# Sallen-Key_Filter.net
KiCad netlist of a schematic drawn in Altium Designer
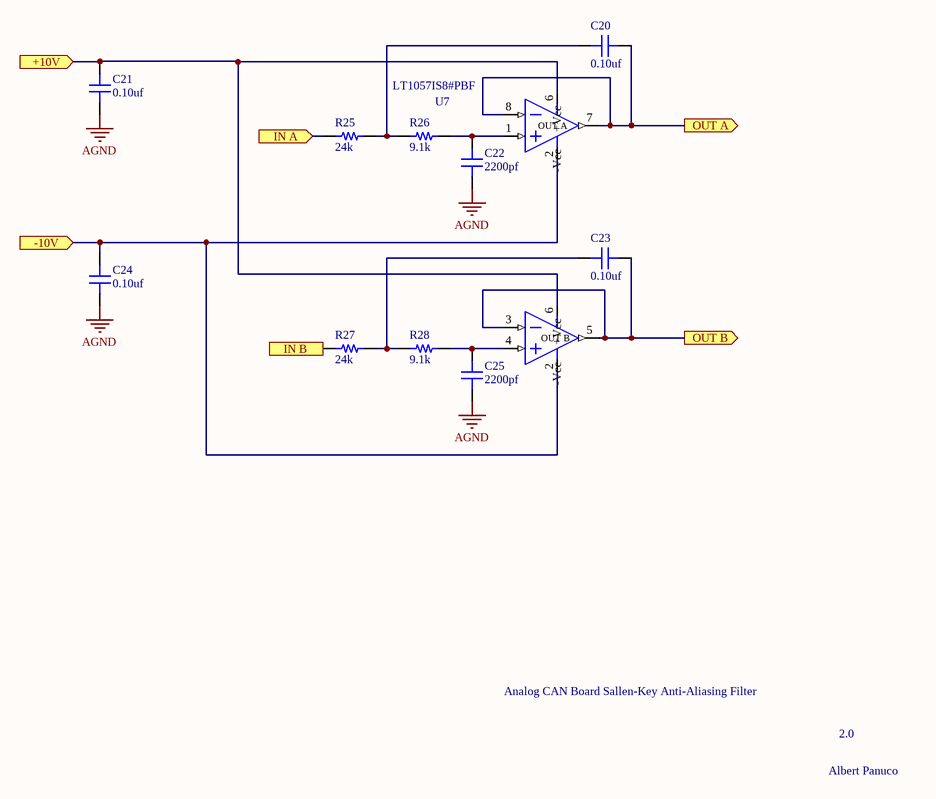
[diagram p0: Sallen-Key Filter.SchDoc]

(export (version "E")
  (design (tool "Eeschema 10.0.6"))
  (components
    (comp (ref "C20")
      (value "0.10uf")
      (footprint "CAP 0805/2012")
      (fields
        (field (name "Comment") "Capacitor MLCC 0.10uf 25V CAP 0805/2012")
        (field (name "CREATED_BY") "Nick Mah")
      )
      (libsource (lib "Altium-Lib") (part "Capacitor"))
    )
    (comp (ref "C21")
      (value "0.10uf")
      (footprint "CAP 0805/2012")
      (fields
        (field (name "Comment") "Capacitor MLCC 0.10uf 25V CAP 0805/2012")
        (field (name "CREATED_BY") "Nick Mah")
      )
      (libsource (lib "Altium-Lib") (part "Capacitor"))
    )
    (comp (ref "C22")
      (value "2200pf")
      (footprint "CAP 0805/2012")
      (fields
        (field (name "Comment") "Capacitor MLCC 2200pf 25V CAP 0805/2012")
        (field (name "CREATED_BY") "Nick Mah")
      )
      (libsource (lib "Altium-Lib") (part "Capacitor"))
    )
    (comp (ref "C23")
      (value "0.10uf")
      (footprint "CAP 0805/2012")
      (fields
        (field (name "Comment") "Capacitor MLCC 0.10uf 25V CAP 0805/2012")
        (field (name "CREATED_BY") "Nick Mah")
      )
      (libsource (lib "Altium-Lib") (part "Capacitor"))
    )
    (comp (ref "C24")
      (value "0.10uf")
      (footprint "CAP 0805/2012")
      (fields
        (field (name "Comment") "Capacitor MLCC 0.10uf 25V CAP 0805/2012")
        (field (name "CREATED_BY") "Nick Mah")
      )
      (libsource (lib "Altium-Lib") (part "Capacitor"))
    )
    (comp (ref "C25")
      (value "2200pf")
      (footprint "CAP 0805/2012")
      (fields
        (field (name "Comment") "Capacitor MLCC 2200pf 25V CAP 0805/2012")
        (field (name "CREATED_BY") "Nick Mah")
      )
      (libsource (lib "Altium-Lib") (part "Capacitor"))
    )
    (comp (ref "R25")
      (value "24k")
      (footprint "RES 0805/2012")
      (fields
        (field (name "TOLERANCE") "1%")
        (field (name "POWER") "1/10W")
        (field (name "Comment") "Resistor 24k 0805 1/10W 1%")
        (field (name "CREATED_BY") "Nick Mah")
      )
      (libsource (lib "Altium-Lib") (part "Resistor"))
    )
    (comp (ref "R26")
      (value "9.1k")
      (footprint "RES 0805/2012")
      (fields
        (field (name "TOLERANCE") "1%")
        (field (name "POWER") "1/10W")
        (field (name "Comment") "Resistor 9.1k 0805 1/10W 1%")
        (field (name "CREATED_BY") "Nick Mah")
      )
      (libsource (lib "Altium-Lib") (part "Resistor"))
    )
    (comp (ref "R27")
      (value "24k")
      (footprint "RES 0805/2012")
      (fields
        (field (name "TOLERANCE") "1%")
        (field (name "POWER") "1/10W")
        (field (name "Comment") "Resistor 24k 0805 1/10W 1%")
        (field (name "CREATED_BY") "Nick Mah")
      )
      (libsource (lib "Altium-Lib") (part "Resistor"))
    )
    (comp (ref "R28")
      (value "9.1k")
      (footprint "RES 0805/2012")
      (fields
        (field (name "TOLERANCE") "1%")
        (field (name "POWER") "1/10W")
        (field (name "Comment") "Resistor 9.1k 0805 1/10W 1%")
        (field (name "CREATED_BY") "Nick Mah")
      )
      (libsource (lib "Altium-Lib") (part "Resistor"))
    )
    (comp (ref "U7")
      (value "LT1057IS8#PBF")
      (footprint "SOIC-8")
      (description "IC OPAMP JFET 5MHZ 8SO")
      (fields (field (name "CREATED_BY") "Albert Panuco"))
      (libsource (lib "Altium-Lib") (part "LT1057IS8#PBF"))
    )
  )
  (nets
    (net (code "1") (name "/+10V") (class "Default")
      (node (ref "C21") (pin "2") (pinfunction "2_2") (pintype "passive"))
      (node (ref "U7") (pin "6") (pinfunction "+Vcc_6") (pintype "input"))
    )
    (net (code "2") (name "/-10V") (class "Default")
      (node (ref "C24") (pin "1") (pinfunction "1_1") (pintype "passive"))
      (node (ref "U7") (pin "2") (pinfunction "-Vcc_2") (pintype "input"))
    )
    (net (code "3") (name "/IN A") (class "Default")
      (node (ref "R25") (pin "1") (pinfunction "1_1") (pintype "passive"))
    )
    (net (code "4") (name "/IN B") (class "Default")
      (node (ref "R27") (pin "1") (pinfunction "1_1") (pintype "passive"))
    )
    (net (code "5") (name "/OUT A") (class "Default")
      (node (ref "C20") (pin "2") (pinfunction "2_2") (pintype "passive"))
      (node (ref "U7") (pin "7") (pinfunction "OUT_A_7") (pintype "output"))
      (node (ref "U7") (pin "8") (pinfunction "-IN_A_8") (pintype "input"))
    )
    (net (code "6") (name "/OUT B") (class "Default")
      (node (ref "C23") (pin "2") (pinfunction "2_2") (pintype "passive"))
      (node (ref "U7") (pin "3") (pinfunction "+IN_B_3") (pintype "input"))
      (node (ref "U7") (pin "5") (pinfunction "OUT_B_5") (pintype "output"))
    )
    (net (code "7") (name "AGND") (class "Default")
      (node (ref "C21") (pin "1") (pinfunction "1_1") (pintype "passive"))
      (node (ref "C22") (pin "1") (pinfunction "1_1") (pintype "passive"))
      (node (ref "C24") (pin "2") (pinfunction "2_2") (pintype "passive"))
      (node (ref "C25") (pin "1") (pinfunction "1_1") (pintype "passive"))
    )
    (net (code "8") (name "Net-(C20-Pad1)") (class "Default")
      (node (ref "C20") (pin "1") (pinfunction "1_1") (pintype "passive"))
      (node (ref "R25") (pin "2") (pinfunction "2_2") (pintype "passive"))
      (node (ref "R26") (pin "1") (pinfunction "1_1") (pintype "passive"))
    )
    (net (code "9") (name "Net-(C23-Pad1)") (class "Default")
      (node (ref "C23") (pin "1") (pinfunction "1_1") (pintype "passive"))
      (node (ref "R27") (pin "2") (pinfunction "2_2") (pintype "passive"))
      (node (ref "R28") (pin "1") (pinfunction "1_1") (pintype "passive"))
    )
    (net (code "10") (name "Net-(C25-Pad2)") (class "Default")
      (node (ref "C25") (pin "2") (pinfunction "2_2") (pintype "passive"))
      (node (ref "R28") (pin "2") (pinfunction "2_2") (pintype "passive"))
      (node (ref "U7") (pin "4") (pinfunction "+IN_B_4") (pintype "input"))
    )
    (net (code "11") (name "Net-(U7-+IN_A)") (class "Default")
      (node (ref "C22") (pin "2") (pinfunction "2_2") (pintype "passive"))
      (node (ref "R26") (pin "2") (pinfunction "2_2") (pintype "passive"))
      (node (ref "U7") (pin "1") (pinfunction "+IN_A_1") (pintype "input"))
    )
  )
)
